# SAMV71_Xplained_Ultra_Connectors.net
KiCad netlist of a schematic drawn in Altium Designer
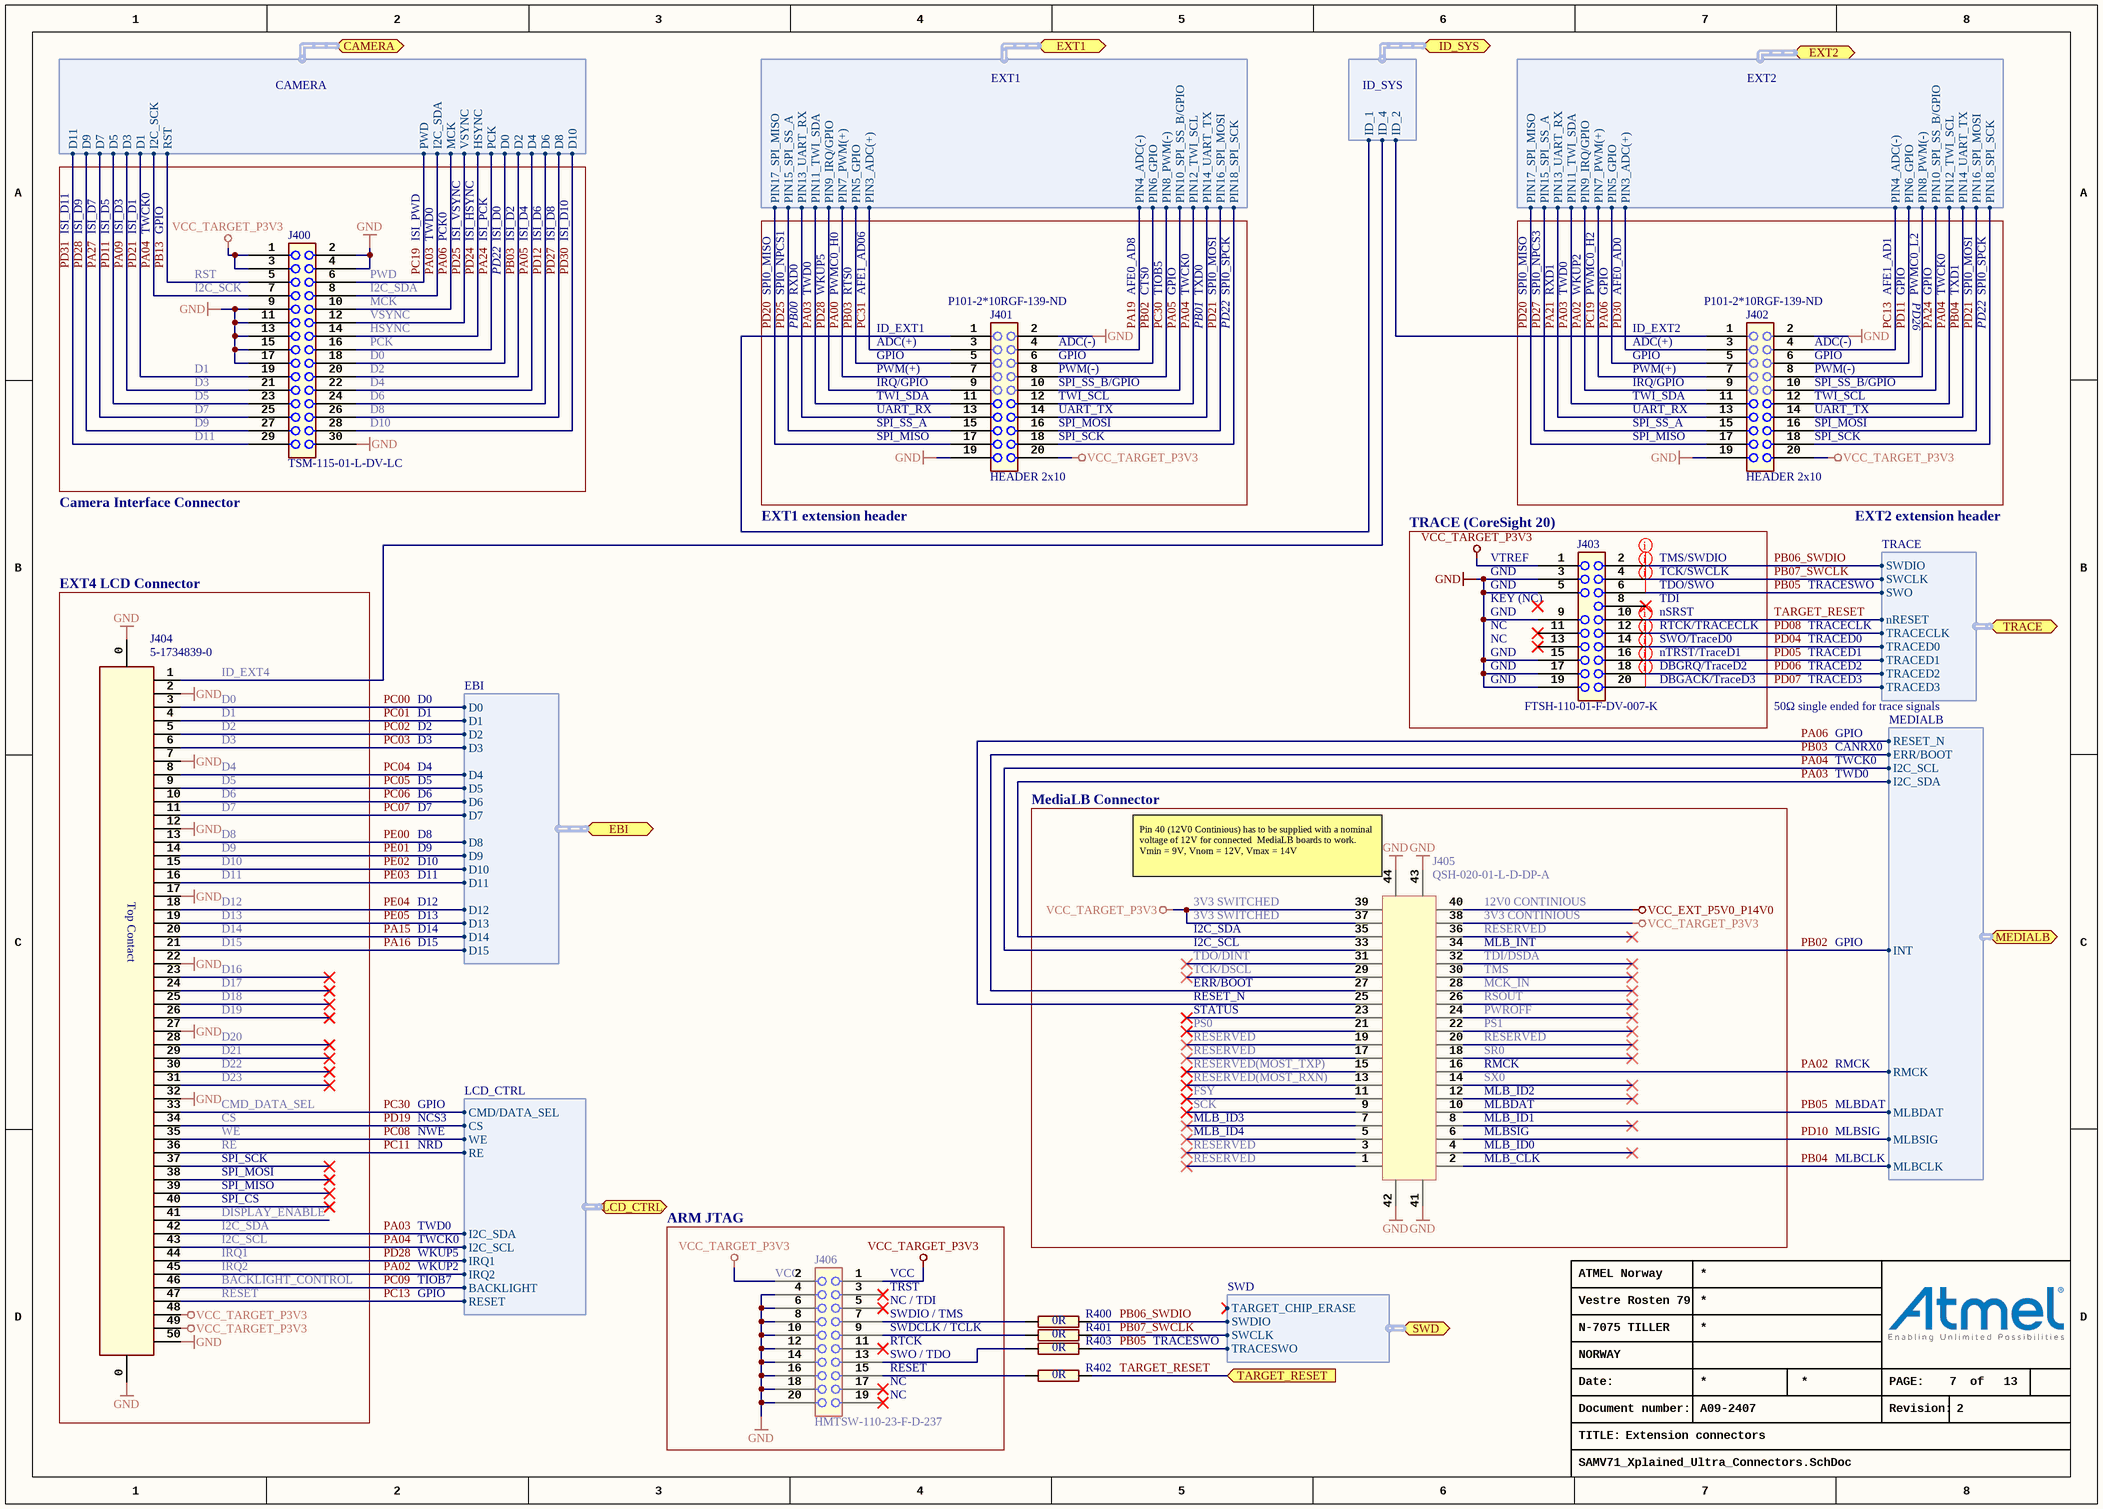
[diagram p0: SAMV71_Xplained_Ultra_Connectors.SchDoc]

(export (version "E")
  (design (tool "Eeschema 10.0.6"))
  (components
    (comp (ref "J400")
      (value "TSM-115-01-L-DV-LC")
      (footprint "AP8-00884")
      (description "Samtec TSM series, 2x15 pin header, straight, 2.54mm pitch SMD, locking leads.")
      (fields (field (name "Comment") "HEADER 2x15"))
      (libsource (lib "AltiumDbLib") (part "HEADER 2x15"))
    )
    (comp (ref "J401")
      (value "HEADER 2x10")
      (footprint "AP8-00622")
      (description "Pin header, 2x10, Right Angle, 2.54mm, THM, Pin In Paste")
      (fields (field (name "ALTIUM_VALUE") "P101-2*10RGF-139-ND") (field (name "MPN") "P101-2*10RGF-139-ND"))
      (libsource (lib "AltiumDbLib") (part "HEADER 2x10"))
    )
    (comp (ref "J402")
      (value "HEADER 2x10")
      (footprint "AP8-00622")
      (description "Pin header, 2x10, Right Angle, 2.54mm, THM, Pin In Paste")
      (fields (field (name "ALTIUM_VALUE") "P101-2*10RGF-139-ND") (field (name "MPN") "P101-2*10RGF-139-ND"))
      (libsource (lib "AltiumDbLib") (part "HEADER 2x10"))
    )
    (comp (ref "J403")
      (value "FTSH-110-01-F-DV-007-K")
      (footprint "AP8-00910")
      (description "SAMTEC FTSH series 50-mil header, shrouded, pin 7 removed, SMD")
      (libsource (lib "AltiumDbLib") (part "FTSH-110-01-F-DV-007-K"))
    )
    (comp (ref "J404")
      (value "5-1734839-0")
      (footprint "AP8-00774")
      (description "50 pin FPC connector, e=0.5mm, single side contact (top).")
      (fields
        (field (name "MANUFACTURER") "TE Connectivity")
        (field (name "Comment") "Used for Xplained Pro MCU board on top layer.")
      )
      (libsource (lib "AltiumDbLib") (part "5-1734839-0"))
    )
    (comp (ref "J405")
      (value "QSH-020-01-L-D-DP-A")
      (footprint "AP8-00878")
      (description "SAMTEC 0.5mm, 20-pair, High-Speed Differential Pair Socket")
      (libsource (lib "AltiumDbLib") (part "QSH-020-01-L-D-DP-A"))
    )
    (comp (ref "J406")
      (value "HMTSW-110-23-F-D-237")
      (footprint "AP8-00744")
      (description "2x10 pin header, 2.54mm pitch, Pin-in-Paste THM, 1mm hole")
      (fields
        (field (name "MANUFACTURER") "SAMTEC")
        (field (name "Comment") "Same as A08-1514 but with 1mm hole")
      )
      (libsource (lib "AltiumDbLib") (part "HEADER 2x10"))
    )
    (comp (ref "R400")
      (value "0R")
      (footprint "AP2-00000")
      (description "RES 0.0 OHM 1/16W 0402 SMD")
      (fields (field (name "TOLERANCE") "1 %") (field (name "MANUFACTURER") "(n/a)"))
      (libsource (lib "AltiumDbLib") (part "R2"))
    )
    (comp (ref "R401")
      (value "0R")
      (footprint "AP2-00000")
      (description "RES 0.0 OHM 1/16W 0402 SMD")
      (fields (field (name "TOLERANCE") "1 %") (field (name "MANUFACTURER") "(n/a)"))
      (libsource (lib "AltiumDbLib") (part "R2"))
    )
    (comp (ref "R402")
      (value "0R")
      (footprint "AP2-00000")
      (description "RES 0.0 OHM 1/16W 0402 SMD")
      (fields (field (name "TOLERANCE") "1 %") (field (name "MANUFACTURER") "(n/a)"))
      (libsource (lib "AltiumDbLib") (part "R2"))
    )
    (comp (ref "R403")
      (value "0R")
      (footprint "AP2-00000")
      (description "RES 0.0 OHM 1/16W 0402 SMD")
      (fields (field (name "TOLERANCE") "1 %") (field (name "MANUFACTURER") "(n/a)"))
      (libsource (lib "AltiumDbLib") (part "R2"))
    )
  )
  (nets
    (net (code "10") (name "/ID_1") (class "Default")
      (node (ref "J401") (pin "1") (pinfunction "1_1") (pintype "passive"))
    )
    (net (code "11") (name "/ID_2") (class "Default")
      (node (ref "J402") (pin "1") (pinfunction "1_1") (pintype "passive"))
    )
    (net (code "12") (name "/ID_4") (class "Default")
      (node (ref "J404") (pin "1") (pinfunction "1_1") (pintype "passive"))
    )
    (net (code "13") (name "/PA00") (class "Default")
      (node (ref "J401") (pin "7") (pinfunction "7_7") (pintype "passive"))
    )
    (net (code "14") (name "/PA02") (class "Default")
      (node (ref "J402") (pin "9") (pinfunction "9_9") (pintype "passive"))
      (node (ref "J404") (pin "45") (pinfunction "45_45") (pintype "passive"))
      (node (ref "J405") (pin "16") (pinfunction "16_16") (pintype "passive"))
    )
    (net (code "15") (name "/PA03") (class "Default")
      (node (ref "J400") (pin "8") (pinfunction "8_8") (pintype "passive"))
      (node (ref "J401") (pin "11") (pinfunction "11_11") (pintype "passive"))
      (node (ref "J402") (pin "11") (pinfunction "11_11") (pintype "passive"))
      (node (ref "J404") (pin "42") (pinfunction "42_42") (pintype "passive"))
      (node (ref "J405") (pin "35") (pinfunction "35_35") (pintype "passive"))
    )
    (net (code "16") (name "/PA04") (class "Default")
      (node (ref "J400") (pin "7") (pinfunction "7_7") (pintype "passive"))
      (node (ref "J401") (pin "12") (pinfunction "12_12") (pintype "passive"))
      (node (ref "J402") (pin "12") (pinfunction "12_12") (pintype "passive"))
      (node (ref "J404") (pin "43") (pinfunction "43_43") (pintype "passive"))
      (node (ref "J405") (pin "33") (pinfunction "33_33") (pintype "passive"))
    )
    (net (code "17") (name "/PA05") (class "Default")
      (node (ref "J400") (pin "22") (pinfunction "22_22") (pintype "passive"))
      (node (ref "J401") (pin "10") (pinfunction "10_10") (pintype "passive"))
    )
    (net (code "18") (name "/PA06") (class "Default")
      (node (ref "J400") (pin "10") (pinfunction "10_10") (pintype "passive"))
      (node (ref "J402") (pin "5") (pinfunction "5_5") (pintype "passive"))
      (node (ref "J405") (pin "25") (pinfunction "25_25") (pintype "passive"))
    )
    (net (code "19") (name "/PA09") (class "Default")
      (node (ref "J400") (pin "21") (pinfunction "21_21") (pintype "passive"))
    )
    (net (code "20") (name "/PA15") (class "Default")
      (node (ref "J404") (pin "20") (pinfunction "20_20") (pintype "passive"))
    )
    (net (code "21") (name "/PA16") (class "Default")
      (node (ref "J404") (pin "21") (pinfunction "21_21") (pintype "passive"))
    )
    (net (code "22") (name "/PA19") (class "Default")
      (node (ref "J401") (pin "4") (pinfunction "4_4") (pintype "passive"))
    )
    (net (code "23") (name "/PA21") (class "Default")
      (node (ref "J402") (pin "13") (pinfunction "13_13") (pintype "passive"))
    )
    (net (code "24") (name "/PA24") (class "Default")
      (node (ref "J400") (pin "16") (pinfunction "16_16") (pintype "passive"))
      (node (ref "J402") (pin "10") (pinfunction "10_10") (pintype "passive"))
    )
    (net (code "25") (name "/PA27") (class "Default")
      (node (ref "J400") (pin "25") (pinfunction "25_25") (pintype "passive"))
    )
    (net (code "26") (name "/PB02") (class "Default")
      (node (ref "J401") (pin "6") (pinfunction "6_6") (pintype "passive"))
      (node (ref "J405") (pin "34") (pinfunction "34_34") (pintype "passive"))
    )
    (net (code "27") (name "/PB03") (class "Default")
      (node (ref "J400") (pin "20") (pinfunction "20_20") (pintype "passive"))
      (node (ref "J401") (pin "5") (pinfunction "5_5") (pintype "passive"))
      (node (ref "J405") (pin "27") (pinfunction "27_27") (pintype "passive"))
    )
    (net (code "28") (name "/PB04") (class "Default")
      (node (ref "J402") (pin "14") (pinfunction "14_14") (pintype "passive"))
      (node (ref "J405") (pin "2") (pinfunction "2_2") (pintype "passive"))
    )
    (net (code "29") (name "/PB05") (class "Default")
      (node (ref "J403") (pin "6") (pinfunction "6_6") (pintype "passive"))
      (node (ref "J405") (pin "10") (pinfunction "10_10") (pintype "passive"))
      (node (ref "R403") (pin "2") (pinfunction "2_2") (pintype "passive"))
    )
    (net (code "30") (name "/PB06_SWDIO") (class "Default")
      (node (ref "J403") (pin "2") (pinfunction "2_2") (pintype "passive"))
      (node (ref "R400") (pin "2") (pinfunction "2_2") (pintype "passive"))
    )
    (net (code "31") (name "/PB07_SWCLK") (class "Default")
      (node (ref "J403") (pin "4") (pinfunction "4_4") (pintype "passive"))
      (node (ref "R401") (pin "2") (pinfunction "2_2") (pintype "passive"))
    )
    (net (code "32") (name "/PB13") (class "Default")
      (node (ref "J400") (pin "5") (pinfunction "5_5") (pintype "passive"))
    )
    (net (code "33") (name "/PC00") (class "Default")
      (node (ref "J404") (pin "3") (pinfunction "3_3") (pintype "passive"))
    )
    (net (code "34") (name "/PC01") (class "Default")
      (node (ref "J404") (pin "4") (pinfunction "4_4") (pintype "passive"))
    )
    (net (code "35") (name "/PC02") (class "Default")
      (node (ref "J404") (pin "5") (pinfunction "5_5") (pintype "passive"))
    )
    (net (code "36") (name "/PC03") (class "Default")
      (node (ref "J404") (pin "6") (pinfunction "6_6") (pintype "passive"))
    )
    (net (code "37") (name "/PC04") (class "Default")
      (node (ref "J404") (pin "8") (pinfunction "8_8") (pintype "passive"))
    )
    (net (code "38") (name "/PC05") (class "Default")
      (node (ref "J404") (pin "9") (pinfunction "9_9") (pintype "passive"))
    )
    (net (code "39") (name "/PC06") (class "Default")
      (node (ref "J404") (pin "10") (pinfunction "10_10") (pintype "passive"))
    )
    (net (code "40") (name "/PC07") (class "Default")
      (node (ref "J404") (pin "11") (pinfunction "11_11") (pintype "passive"))
    )
    (net (code "41") (name "/PC08") (class "Default")
      (node (ref "J404") (pin "35") (pinfunction "35_35") (pintype "passive"))
    )
    (net (code "42") (name "/PC09") (class "Default")
      (node (ref "J404") (pin "46") (pinfunction "46_46") (pintype "passive"))
    )
    (net (code "43") (name "/PC11") (class "Default")
      (node (ref "J404") (pin "36") (pinfunction "36_36") (pintype "passive"))
    )
    (net (code "44") (name "/PC13") (class "Default")
      (node (ref "J402") (pin "4") (pinfunction "4_4") (pintype "passive"))
      (node (ref "J404") (pin "47") (pinfunction "47_47") (pintype "passive"))
    )
    (net (code "45") (name "/PC19") (class "Default")
      (node (ref "J400") (pin "6") (pinfunction "6_6") (pintype "passive"))
      (node (ref "J402") (pin "7") (pinfunction "7_7") (pintype "passive"))
    )
    (net (code "46") (name "/PC30") (class "Default")
      (node (ref "J401") (pin "8") (pinfunction "8_8") (pintype "passive"))
      (node (ref "J404") (pin "33") (pinfunction "33_33") (pintype "passive"))
    )
    (net (code "47") (name "/PC31") (class "Default")
      (node (ref "J401") (pin "3") (pinfunction "3_3") (pintype "passive"))
    )
    (net (code "48") (name "/PD04") (class "Default")
      (node (ref "J403") (pin "14") (pinfunction "14_14") (pintype "passive"))
    )
    (net (code "49") (name "/PD05") (class "Default")
      (node (ref "J403") (pin "16") (pinfunction "16_16") (pintype "passive"))
    )
    (net (code "50") (name "/PD06") (class "Default")
      (node (ref "J403") (pin "18") (pinfunction "18_18") (pintype "passive"))
    )
    (net (code "51") (name "/PD07") (class "Default")
      (node (ref "J403") (pin "20") (pinfunction "20_20") (pintype "passive"))
    )
    (net (code "52") (name "/PD08") (class "Default")
      (node (ref "J403") (pin "12") (pinfunction "12_12") (pintype "passive"))
    )
    (net (code "53") (name "/PD10") (class "Default")
      (node (ref "J405") (pin "6") (pinfunction "6_6") (pintype "passive"))
    )
    (net (code "54") (name "/PD11") (class "Default")
      (node (ref "J400") (pin "23") (pinfunction "23_23") (pintype "passive"))
      (node (ref "J402") (pin "6") (pinfunction "6_6") (pintype "passive"))
    )
    (net (code "55") (name "/PD12") (class "Default")
      (node (ref "J400") (pin "24") (pinfunction "24_24") (pintype "passive"))
    )
    (net (code "56") (name "/PD19") (class "Default")
      (node (ref "J404") (pin "34") (pinfunction "34_34") (pintype "passive"))
    )
    (net (code "57") (name "/PD20") (class "Default")
      (node (ref "J401") (pin "17") (pinfunction "17_17") (pintype "passive"))
      (node (ref "J402") (pin "17") (pinfunction "17_17") (pintype "passive"))
    )
    (net (code "58") (name "/PD21") (class "Default")
      (node (ref "J400") (pin "19") (pinfunction "19_19") (pintype "passive"))
      (node (ref "J401") (pin "16") (pinfunction "16_16") (pintype "passive"))
      (node (ref "J402") (pin "16") (pinfunction "16_16") (pintype "passive"))
    )
    (net (code "59") (name "/PD24") (class "Default")
      (node (ref "J400") (pin "14") (pinfunction "14_14") (pintype "passive"))
    )
    (net (code "60") (name "/PD25") (class "Default")
      (node (ref "J400") (pin "12") (pinfunction "12_12") (pintype "passive"))
      (node (ref "J401") (pin "15") (pinfunction "15_15") (pintype "passive"))
    )
    (net (code "61") (name "/PD27") (class "Default")
      (node (ref "J400") (pin "26") (pinfunction "26_26") (pintype "passive"))
      (node (ref "J402") (pin "15") (pinfunction "15_15") (pintype "passive"))
    )
    (net (code "62") (name "/PD28") (class "Default")
      (node (ref "J400") (pin "27") (pinfunction "27_27") (pintype "passive"))
      (node (ref "J401") (pin "9") (pinfunction "9_9") (pintype "passive"))
      (node (ref "J404") (pin "44") (pinfunction "44_44") (pintype "passive"))
    )
    (net (code "63") (name "/PD30") (class "Default")
      (node (ref "J400") (pin "28") (pinfunction "28_28") (pintype "passive"))
      (node (ref "J402") (pin "3") (pinfunction "3_3") (pintype "passive"))
    )
    (net (code "64") (name "/PD31") (class "Default")
      (node (ref "J400") (pin "29") (pinfunction "29_29") (pintype "passive"))
    )
    (net (code "65") (name "/PE00") (class "Default")
      (node (ref "J404") (pin "13") (pinfunction "13_13") (pintype "passive"))
    )
    (net (code "66") (name "/PE01") (class "Default")
      (node (ref "J404") (pin "14") (pinfunction "14_14") (pintype "passive"))
    )
    (net (code "67") (name "/PE02") (class "Default")
      (node (ref "J404") (pin "15") (pinfunction "15_15") (pintype "passive"))
    )
    (net (code "68") (name "/PE03") (class "Default")
      (node (ref "J404") (pin "16") (pinfunction "16_16") (pintype "passive"))
    )
    (net (code "69") (name "/PE04") (class "Default")
      (node (ref "J404") (pin "18") (pinfunction "18_18") (pintype "passive"))
    )
    (net (code "70") (name "/PE05") (class "Default")
      (node (ref "J404") (pin "19") (pinfunction "19_19") (pintype "passive"))
    )
    (net (code "71") (name "/TARGET_RESET") (class "Default")
      (node (ref "J403") (pin "10") (pinfunction "10_10") (pintype "passive"))
      (node (ref "R402") (pin "2") (pinfunction "2_2") (pintype "passive"))
    )
    (net (code "81") (name "GND") (class "Default")
      (node (ref "J400") (pin "11") (pinfunction "11_11") (pintype "passive"))
      (node (ref "J400") (pin "13") (pinfunction "13_13") (pintype "passive"))
      (node (ref "J400") (pin "15") (pinfunction "15_15") (pintype "passive"))
      (node (ref "J400") (pin "17") (pinfunction "17_17") (pintype "passive"))
      (node (ref "J400") (pin "2") (pinfunction "2_2") (pintype "passive"))
      (node (ref "J400") (pin "30") (pinfunction "30_30") (pintype "passive"))
      (node (ref "J400") (pin "4") (pinfunction "4_4") (pintype "passive"))
      (node (ref "J400") (pin "9") (pinfunction "9_9") (pintype "passive"))
      (node (ref "J401") (pin "19") (pinfunction "19_19") (pintype "passive"))
      (node (ref "J401") (pin "2") (pinfunction "2_2") (pintype "passive"))
      (node (ref "J402") (pin "19") (pinfunction "19_19") (pintype "passive"))
      (node (ref "J402") (pin "2") (pinfunction "2_2") (pintype "passive"))
      (node (ref "J403") (pin "15") (pinfunction "15_15") (pintype "passive"))
      (node (ref "J403") (pin "17") (pinfunction "17_17") (pintype "passive"))
      (node (ref "J403") (pin "19") (pinfunction "19_19") (pintype "passive"))
      (node (ref "J403") (pin "3") (pinfunction "3_3") (pintype "passive"))
      (node (ref "J403") (pin "5") (pinfunction "5_5") (pintype "passive"))
      (node (ref "J403") (pin "9") (pinfunction "9_9") (pintype "passive"))
      (node (ref "J404") (pin "0") (pinfunction "1_0") (pintype "passive"))
      (node (ref "J404") (pin "12") (pinfunction "12_12") (pintype "passive"))
      (node (ref "J404") (pin "17") (pinfunction "17_17") (pintype "passive"))
      (node (ref "J404") (pin "2") (pinfunction "2_2") (pintype "passive"))
      (node (ref "J404") (pin "22") (pinfunction "22_22") (pintype "passive"))
      (node (ref "J404") (pin "27") (pinfunction "27_27") (pintype "passive"))
      (node (ref "J404") (pin "32") (pinfunction "32_32") (pintype "passive"))
      (node (ref "J404") (pin "50") (pinfunction "50_50") (pintype "passive"))
      (node (ref "J404") (pin "7") (pinfunction "7_7") (pintype "passive"))
      (node (ref "J405") (pin "41") (pinfunction "41_41") (pintype "passive"))
      (node (ref "J405") (pin "42") (pinfunction "42_42") (pintype "passive"))
      (node (ref "J405") (pin "43") (pinfunction "43_43") (pintype "passive"))
      (node (ref "J405") (pin "44") (pinfunction "44_44") (pintype "passive"))
      (node (ref "J406") (pin "10") (pinfunction "10_10") (pintype "passive"))
      (node (ref "J406") (pin "12") (pinfunction "12_12") (pintype "passive"))
      (node (ref "J406") (pin "14") (pinfunction "14_14") (pintype "passive"))
      (node (ref "J406") (pin "16") (pinfunction "16_16") (pintype "passive"))
      (node (ref "J406") (pin "18") (pinfunction "18_18") (pintype "passive"))
      (node (ref "J406") (pin "20") (pinfunction "20_20") (pintype "passive"))
      (node (ref "J406") (pin "4") (pinfunction "4_4") (pintype "passive"))
      (node (ref "J406") (pin "6") (pinfunction "6_6") (pintype "passive"))
      (node (ref "J406") (pin "8") (pinfunction "8_8") (pintype "passive"))
    )
    (net (code "82") (name "Net-(J406-Pad7)") (class "Default")
      (node (ref "J406") (pin "7") (pinfunction "7_7") (pintype "passive"))
      (node (ref "R400") (pin "1") (pinfunction "1_1") (pintype "passive"))
    )
    (net (code "83") (name "Net-(J406-Pad9)") (class "Default")
      (node (ref "J406") (pin "9") (pinfunction "9_9") (pintype "passive"))
      (node (ref "R401") (pin "1") (pinfunction "1_1") (pintype "passive"))
    )
    (net (code "84") (name "Net-(J406-Pad13)") (class "Default")
      (node (ref "J406") (pin "13") (pinfunction "13_13") (pintype "passive"))
      (node (ref "R403") (pin "1") (pinfunction "1_1") (pintype "passive"))
    )
    (net (code "85") (name "Net-(J406-Pad15)") (class "Default")
      (node (ref "J406") (pin "15") (pinfunction "15_15") (pintype "passive"))
      (node (ref "R402") (pin "1") (pinfunction "1_1") (pintype "passive"))
    )
    (net (code "86") (name "VCC_EXT_P5V0_P14V0") (class "Default")
      (node (ref "J405") (pin "40") (pinfunction "40_40") (pintype "passive"))
    )
    (net (code "87") (name "VCC_TARGET_P3V3") (class "Default")
      (node (ref "J400") (pin "1") (pinfunction "1_1") (pintype "passive"))
      (node (ref "J400") (pin "3") (pinfunction "3_3") (pintype "passive"))
      (node (ref "J401") (pin "20") (pinfunction "20_20") (pintype "passive"))
      (node (ref "J402") (pin "20") (pinfunction "20_20") (pintype "passive"))
      (node (ref "J403") (pin "1") (pinfunction "1_1") (pintype "passive"))
      (node (ref "J404") (pin "48") (pinfunction "48_48") (pintype "passive"))
      (node (ref "J404") (pin "49") (pinfunction "49_49") (pintype "passive"))
      (node (ref "J405") (pin "37") (pinfunction "37_37") (pintype "passive"))
      (node (ref "J405") (pin "38") (pinfunction "38_38") (pintype "passive"))
      (node (ref "J405") (pin "39") (pinfunction "39_39") (pintype "passive"))
      (node (ref "J406") (pin "1") (pinfunction "1_1") (pintype "passive"))
      (node (ref "J406") (pin "2") (pinfunction "2_2") (pintype "passive"))
    )
    (net (code "88") (name "unconnected-(J400-Pad18)") (class "Default")
      (node (ref "J400") (pin "18") (pinfunction "18_18") (pintype "passive"))
    )
    (net (code "89") (name "unconnected-(J401-Pad13)") (class "Default")
      (node (ref "J401") (pin "13") (pinfunction "13_13") (pintype "passive"))
    )
    (net (code "90") (name "unconnected-(J401-Pad14)") (class "Default")
      (node (ref "J401") (pin "14") (pinfunction "14_14") (pintype "passive"))
    )
    (net (code "91") (name "unconnected-(J401-Pad18)") (class "Default")
      (node (ref "J401") (pin "18") (pinfunction "18_18") (pintype "passive"))
    )
    (net (code "92") (name "unconnected-(J402-Pad8)") (class "Default")
      (node (ref "J402") (pin "8") (pinfunction "8_8") (pintype "passive"))
    )
    (net (code "93") (name "unconnected-(J402-Pad18)") (class "Default")
      (node (ref "J402") (pin "18") (pinfunction "18_18") (pintype "passive"))
    )
    (net (code "94") (name "unconnected-(J403-Pad8)") (class "Default")
      (node (ref "J403") (pin "8") (pinfunction "8_8") (pintype "passive+no_connect"))
    )
    (net (code "95") (name "unconnected-(J403-Pad11)") (class "Default")
      (node (ref "J403") (pin "11") (pinfunction "11_11") (pintype "passive+no_connect"))
    )
    (net (code "96") (name "unconnected-(J403-Pad13)") (class "Default")
      (node (ref "J403") (pin "13") (pinfunction "13_13") (pintype "passive+no_connect"))
    )
    (net (code "97") (name "unconnected-(J404-Pad23)") (class "Default")
      (node (ref "J404") (pin "23") (pinfunction "23_23") (pintype "passive+no_connect"))
    )
    (net (code "98") (name "unconnected-(J404-Pad24)") (class "Default")
      (node (ref "J404") (pin "24") (pinfunction "24_24") (pintype "passive+no_connect"))
    )
    (net (code "99") (name "unconnected-(J404-Pad25)") (class "Default")
      (node (ref "J404") (pin "25") (pinfunction "25_25") (pintype "passive+no_connect"))
    )
    (net (code "100") (name "unconnected-(J404-Pad26)") (class "Default")
      (node (ref "J404") (pin "26") (pinfunction "26_26") (pintype "passive+no_connect"))
    )
    (net (code "101") (name "unconnected-(J404-Pad28)") (class "Default")
      (node (ref "J404") (pin "28") (pinfunction "28_28") (pintype "passive+no_connect"))
    )
    (net (code "102") (name "unconnected-(J404-Pad29)") (class "Default")
      (node (ref "J404") (pin "29") (pinfunction "29_29") (pintype "passive+no_connect"))
    )
    (net (code "103") (name "unconnected-(J404-Pad30)") (class "Default")
      (node (ref "J404") (pin "30") (pinfunction "30_30") (pintype "passive+no_connect"))
    )
    (net (code "104") (name "unconnected-(J404-Pad31)") (class "Default")
      (node (ref "J404") (pin "31") (pinfunction "31_31") (pintype "passive+no_connect"))
    )
    (net (code "105") (name "unconnected-(J404-Pad37)") (class "Default")
      (node (ref "J404") (pin "37") (pinfunction "37_37") (pintype "passive+no_connect"))
    )
    (net (code "106") (name "unconnected-(J404-Pad38)") (class "Default")
      (node (ref "J404") (pin "38") (pinfunction "38_38") (pintype "passive+no_connect"))
    )
    (net (code "107") (name "unconnected-(J404-Pad39)") (class "Default")
      (node (ref "J404") (pin "39") (pinfunction "39_39") (pintype "passive+no_connect"))
    )
    (net (code "108") (name "unconnected-(J404-Pad40)") (class "Default")
      (node (ref "J404") (pin "40") (pinfunction "40_40") (pintype "passive+no_connect"))
    )
    (net (code "109") (name "unconnected-(J404-Pad41)") (class "Default")
      (node (ref "J404") (pin "41") (pinfunction "41_41") (pintype "passive"))
    )
    (net (code "110") (name "unconnected-(J405-Pad1)") (class "Default")
      (node (ref "J405") (pin "1") (pinfunction "1_1") (pintype "passive+no_connect"))
    )
    (net (code "111") (name "unconnected-(J405-Pad3)") (class "Default")
      (node (ref "J405") (pin "3") (pinfunction "3_3") (pintype "passive+no_connect"))
    )
    (net (code "112") (name "unconnected-(J405-Pad4)") (class "Default")
      (node (ref "J405") (pin "4") (pinfunction "4_4") (pintype "passive+no_connect"))
    )
    (net (code "113") (name "unconnected-(J405-Pad5)") (class "Default")
      (node (ref "J405") (pin "5") (pinfunction "5_5") (pintype "passive+no_connect"))
    )
    (net (code "114") (name "unconnected-(J405-Pad7)") (class "Default")
      (node (ref "J405") (pin "7") (pinfunction "7_7") (pintype "passive+no_connect"))
    )
    (net (code "115") (name "unconnected-(J405-Pad8)") (class "Default")
      (node (ref "J405") (pin "8") (pinfunction "8_8") (pintype "passive+no_connect"))
    )
    (net (code "116") (name "unconnected-(J405-Pad9)") (class "Default")
      (node (ref "J405") (pin "9") (pinfunction "9_9") (pintype "passive+no_connect"))
    )
    (net (code "117") (name "unconnected-(J405-Pad11)") (class "Default")
      (node (ref "J405") (pin "11") (pinfunction "11_11") (pintype "passive+no_connect"))
    )
    (net (code "118") (name "unconnected-(J405-Pad12)") (class "Default")
      (node (ref "J405") (pin "12") (pinfunction "12_12") (pintype "passive+no_connect"))
    )
    (net (code "119") (name "unconnected-(J405-Pad13)") (class "Default")
      (node (ref "J405") (pin "13") (pinfunction "13_13") (pintype "passive+no_connect"))
    )
    (net (code "120") (name "unconnected-(J405-Pad14)") (class "Default")
      (node (ref "J405") (pin "14") (pinfunction "14_14") (pintype "passive+no_connect"))
    )
    (net (code "121") (name "unconnected-(J405-Pad15)") (class "Default")
      (node (ref "J405") (pin "15") (pinfunction "15_15") (pintype "passive+no_connect"))
    )
    (net (code "122") (name "unconnected-(J405-Pad17)") (class "Default")
      (node (ref "J405") (pin "17") (pinfunction "17_17") (pintype "passive+no_connect"))
    )
    (net (code "123") (name "unconnected-(J405-Pad18)") (class "Default")
      (node (ref "J405") (pin "18") (pinfunction "18_18") (pintype "passive+no_connect"))
    )
    (net (code "124") (name "unconnected-(J405-Pad19)") (class "Default")
      (node (ref "J405") (pin "19") (pinfunction "19_19") (pintype "passive+no_connect"))
    )
    (net (code "125") (name "unconnected-(J405-Pad20)") (class "Default")
      (node (ref "J405") (pin "20") (pinfunction "20_20") (pintype "passive+no_connect"))
    )
    (net (code "126") (name "unconnected-(J405-Pad21)") (class "Default")
      (node (ref "J405") (pin "21") (pinfunction "21_21") (pintype "passive+no_connect"))
    )
    (net (code "127") (name "unconnected-(J405-Pad22)") (class "Default")
      (node (ref "J405") (pin "22") (pinfunction "22_22") (pintype "passive+no_connect"))
    )
    (net (code "128") (name "unconnected-(J405-Pad23)") (class "Default")
      (node (ref "J405") (pin "23") (pinfunction "23_23") (pintype "passive+no_connect"))
    )
    (net (code "129") (name "unconnected-(J405-Pad24)") (class "Default")
      (node (ref "J405") (pin "24") (pinfunction "24_24") (pintype "passive+no_connect"))
    )
    (net (code "130") (name "unconnected-(J405-Pad26)") (class "Default")
      (node (ref "J405") (pin "26") (pinfunction "26_26") (pintype "passive+no_connect"))
    )
    (net (code "131") (name "unconnected-(J405-Pad28)") (class "Default")
      (node (ref "J405") (pin "28") (pinfunction "28_28") (pintype "passive+no_connect"))
    )
    (net (code "132") (name "unconnected-(J405-Pad29)") (class "Default")
      (node (ref "J405") (pin "29") (pinfunction "29_29") (pintype "passive+no_connect"))
    )
    (net (code "133") (name "unconnected-(J405-Pad30)") (class "Default")
      (node (ref "J405") (pin "30") (pinfunction "30_30") (pintype "passive+no_connect"))
    )
    (net (code "134") (name "unconnected-(J405-Pad31)") (class "Default")
      (node (ref "J405") (pin "31") (pinfunction "31_31") (pintype "passive+no_connect"))
    )
    (net (code "135") (name "unconnected-(J405-Pad32)") (class "Default")
      (node (ref "J405") (pin "32") (pinfunction "32_32") (pintype "passive+no_connect"))
    )
    (net (code "136") (name "unconnected-(J405-Pad36)") (class "Default")
      (node (ref "J405") (pin "36") (pinfunction "36_36") (pintype "passive+no_connect"))
    )
    (net (code "137") (name "unconnected-(J406-Pad3)") (class "Default")
      (node (ref "J406") (pin "3") (pinfunction "3_3") (pintype "passive+no_connect"))
    )
    (net (code "138") (name "unconnected-(J406-Pad5)") (class "Default")
      (node (ref "J406") (pin "5") (pinfunction "5_5") (pintype "passive+no_connect"))
    )
    (net (code "139") (name "unconnected-(J406-Pad11)") (class "Default")
      (node (ref "J406") (pin "11") (pinfunction "11_11") (pintype "passive+no_connect"))
    )
    (net (code "140") (name "unconnected-(J406-Pad17)") (class "Default")
      (node (ref "J406") (pin "17") (pinfunction "17_17") (pintype "passive+no_connect"))
    )
    (net (code "141") (name "unconnected-(J406-Pad19)") (class "Default")
      (node (ref "J406") (pin "19") (pinfunction "19_19") (pintype "passive+no_connect"))
    )
  )
)
